# Level-Shifter-74244_v10.net
KiCad netlist of a schematic drawn in EAGLE
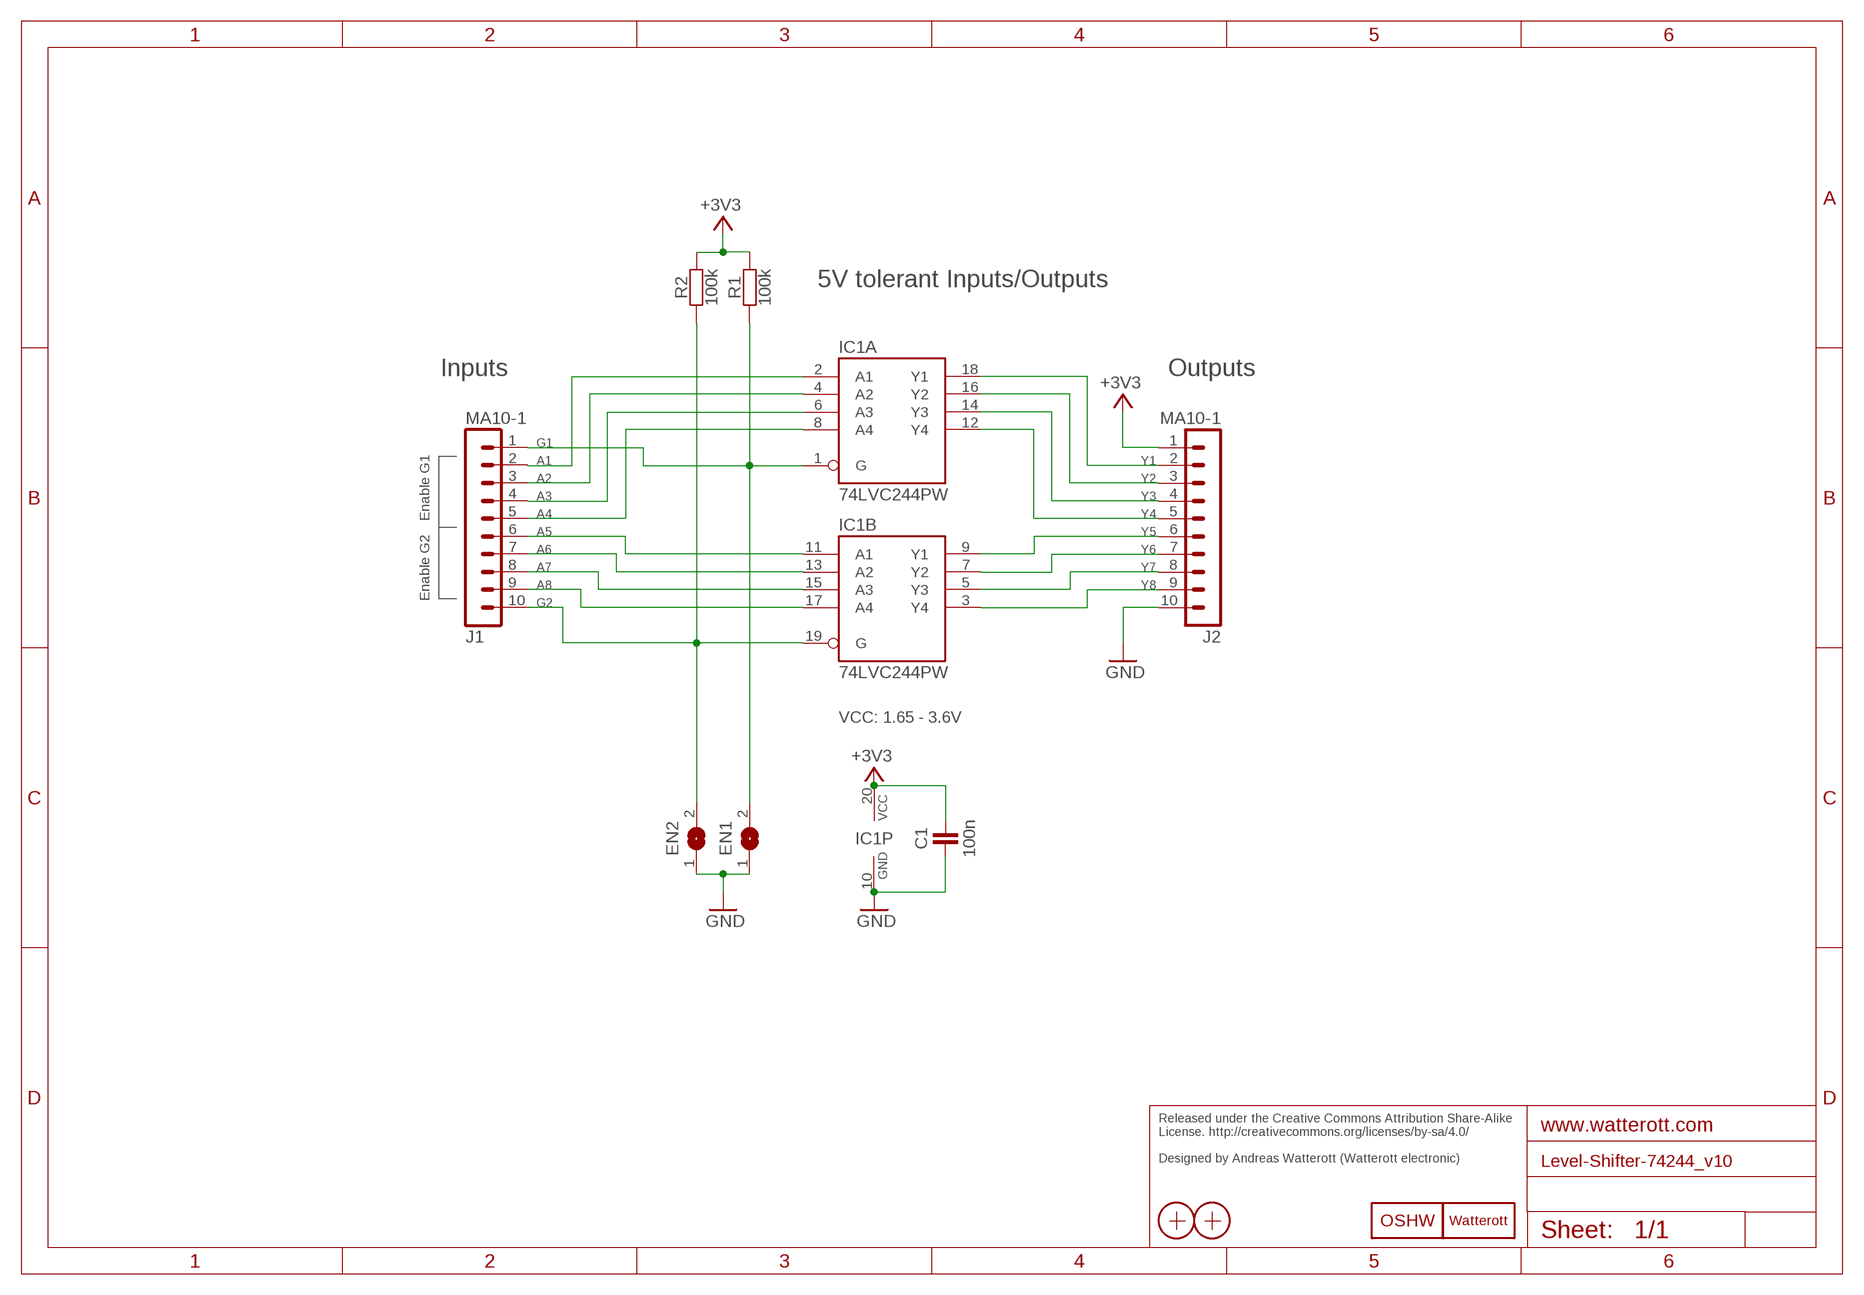
[diagram p0: schematic, sheet 1]

(export (version "E")
  (design (tool "Eeschema 10.0.6"))
  (components
    (comp (ref "C1")
      (value "100n")
      (footprint "eagle-import:C0402")
      (libsource (lib "eagle-import") (part "CAPACITOR-0402"))
    )
    (comp (ref "EN1")
      (value "JUMPER2-0603-NC")
      (footprint "eagle-import:JUMPER2-0603_NC")
      (libsource (lib "eagle-import") (part "JUMPER2-0603-NC"))
    )
    (comp (ref "EN2")
      (value "JUMPER2-0603-NC")
      (footprint "eagle-import:JUMPER2-0603_NC")
      (libsource (lib "eagle-import") (part "JUMPER2-0603-NC"))
    )
    (comp (ref "IC1")
      (value "74LVC244PW")
      (footprint "eagle-import:TSSOP20")
      (libsource (lib "eagle-import") (part "74244PWLVC"))
    )
    (comp (ref "J1")
      (value "MA10-1")
      (footprint "eagle-import:MA10-1")
      (libsource (lib "eagle-import") (part "MA10-1"))
    )
    (comp (ref "J2")
      (value "MA10-1")
      (footprint "eagle-import:MA10-1")
      (libsource (lib "eagle-import") (part "MA10-1"))
    )
    (comp (ref "LOGO1")
      (value "OSHW_LOGOX0070")
      (footprint "eagle-import:OSHW_6X70")
      (libsource (lib "eagle-import") (part "OSHW_LOGOX0070"))
    )
    (comp (ref "LOGO2")
      (value "LOGO-S_PLACE_S")
      (footprint "eagle-import:SPARK_TPLACE_S")
      (libsource (lib "eagle-import") (part "LOGO-S_PLACE_S"))
    )
    (comp (ref "R1")
      (value "100k")
      (footprint "eagle-import:C0402")
      (libsource (lib "eagle-import") (part "RESISTOR-0402"))
    )
    (comp (ref "R2")
      (value "100k")
      (footprint "eagle-import:C0402")
      (libsource (lib "eagle-import") (part "RESISTOR-0402"))
    )
    (comp (ref "X1")
      (value "PASSER-07")
      (footprint "eagle-import:PASSER_07MM")
      (libsource (lib "eagle-import") (part "PASSER-07"))
    )
    (comp (ref "X2")
      (value "PASSER-07")
      (footprint "eagle-import:PASSER_07MM")
      (libsource (lib "eagle-import") (part "PASSER-07"))
    )
  )
  (nets
    (net (code "1") (name "+3V3") (class "Default")
      (node (ref "C1") (pin "2") (pinfunction "2_2") (pintype "passive"))
      (node (ref "IC1") (pin "20") (pinfunction "VCC_20") (pintype "power_in"))
      (node (ref "J2") (pin "1") (pinfunction "1_1") (pintype "passive"))
      (node (ref "R1") (pin "2") (pinfunction "2_2") (pintype "passive"))
      (node (ref "R2") (pin "2") (pinfunction "2_2") (pintype "passive"))
    )
    (net (code "2") (name "/A1") (class "Default")
      (node (ref "IC1") (pin "2") (pinfunction "A1_2") (pintype "input"))
      (node (ref "J1") (pin "2") (pinfunction "2_2") (pintype "passive"))
    )
    (net (code "3") (name "/A2") (class "Default")
      (node (ref "IC1") (pin "4") (pinfunction "A2_4") (pintype "input"))
      (node (ref "J1") (pin "3") (pinfunction "3_3") (pintype "passive"))
    )
    (net (code "4") (name "/A3") (class "Default")
      (node (ref "IC1") (pin "6") (pinfunction "A3_6") (pintype "input"))
      (node (ref "J1") (pin "4") (pinfunction "4_4") (pintype "passive"))
    )
    (net (code "5") (name "/A4") (class "Default")
      (node (ref "IC1") (pin "8") (pinfunction "A4_8") (pintype "input"))
      (node (ref "J1") (pin "5") (pinfunction "5_5") (pintype "passive"))
    )
    (net (code "6") (name "/A5") (class "Default")
      (node (ref "IC1") (pin "11") (pinfunction "A1_11") (pintype "input"))
      (node (ref "J1") (pin "6") (pinfunction "6_6") (pintype "passive"))
    )
    (net (code "7") (name "/A6") (class "Default")
      (node (ref "IC1") (pin "13") (pinfunction "A2_13") (pintype "input"))
      (node (ref "J1") (pin "7") (pinfunction "7_7") (pintype "passive"))
    )
    (net (code "8") (name "/A7") (class "Default")
      (node (ref "IC1") (pin "15") (pinfunction "A3_15") (pintype "input"))
      (node (ref "J1") (pin "8") (pinfunction "8_8") (pintype "passive"))
    )
    (net (code "9") (name "/A8") (class "Default")
      (node (ref "IC1") (pin "17") (pinfunction "A4_17") (pintype "input"))
      (node (ref "J1") (pin "9") (pinfunction "9_9") (pintype "passive"))
    )
    (net (code "10") (name "/G1") (class "Default")
      (node (ref "EN1") (pin "2") (pinfunction "2_2") (pintype "passive"))
      (node (ref "IC1") (pin "1") (pinfunction "G_1") (pintype "input"))
      (node (ref "J1") (pin "1") (pinfunction "1_1") (pintype "passive"))
      (node (ref "R1") (pin "1") (pinfunction "1_1") (pintype "passive"))
    )
    (net (code "11") (name "/G2") (class "Default")
      (node (ref "EN2") (pin "2") (pinfunction "2_2") (pintype "passive"))
      (node (ref "IC1") (pin "19") (pinfunction "G_19") (pintype "input"))
      (node (ref "J1") (pin "10") (pinfunction "10_10") (pintype "passive"))
      (node (ref "R2") (pin "1") (pinfunction "1_1") (pintype "passive"))
    )
    (net (code "12") (name "/Y1") (class "Default")
      (node (ref "IC1") (pin "18") (pinfunction "Y1_18") (pintype "tri_state"))
      (node (ref "J2") (pin "2") (pinfunction "2_2") (pintype "passive"))
    )
    (net (code "13") (name "/Y2") (class "Default")
      (node (ref "IC1") (pin "16") (pinfunction "Y2_16") (pintype "tri_state"))
      (node (ref "J2") (pin "3") (pinfunction "3_3") (pintype "passive"))
    )
    (net (code "14") (name "/Y3") (class "Default")
      (node (ref "IC1") (pin "14") (pinfunction "Y3_14") (pintype "tri_state"))
      (node (ref "J2") (pin "4") (pinfunction "4_4") (pintype "passive"))
    )
    (net (code "15") (name "/Y4") (class "Default")
      (node (ref "IC1") (pin "12") (pinfunction "Y4_12") (pintype "tri_state"))
      (node (ref "J2") (pin "5") (pinfunction "5_5") (pintype "passive"))
    )
    (net (code "16") (name "/Y5") (class "Default")
      (node (ref "IC1") (pin "9") (pinfunction "Y1_9") (pintype "tri_state"))
      (node (ref "J2") (pin "6") (pinfunction "6_6") (pintype "passive"))
    )
    (net (code "17") (name "/Y6") (class "Default")
      (node (ref "IC1") (pin "7") (pinfunction "Y2_7") (pintype "tri_state"))
      (node (ref "J2") (pin "7") (pinfunction "7_7") (pintype "passive"))
    )
    (net (code "18") (name "/Y7") (class "Default")
      (node (ref "IC1") (pin "5") (pinfunction "Y3_5") (pintype "tri_state"))
      (node (ref "J2") (pin "8") (pinfunction "8_8") (pintype "passive"))
    )
    (net (code "19") (name "/Y8") (class "Default")
      (node (ref "IC1") (pin "3") (pinfunction "Y4_3") (pintype "tri_state"))
      (node (ref "J2") (pin "9") (pinfunction "9_9") (pintype "passive"))
    )
    (net (code "20") (name "GND") (class "Default")
      (node (ref "C1") (pin "1") (pinfunction "1_1") (pintype "passive"))
      (node (ref "EN1") (pin "1") (pinfunction "1_1") (pintype "passive"))
      (node (ref "EN2") (pin "1") (pinfunction "1_1") (pintype "passive"))
      (node (ref "IC1") (pin "10") (pinfunction "GND_10") (pintype "power_in"))
      (node (ref "J2") (pin "10") (pinfunction "10_10") (pintype "passive"))
    )
  )
)
